# NinjaPool-171009.net
KiCad netlist of a schematic drawn in EAGLE
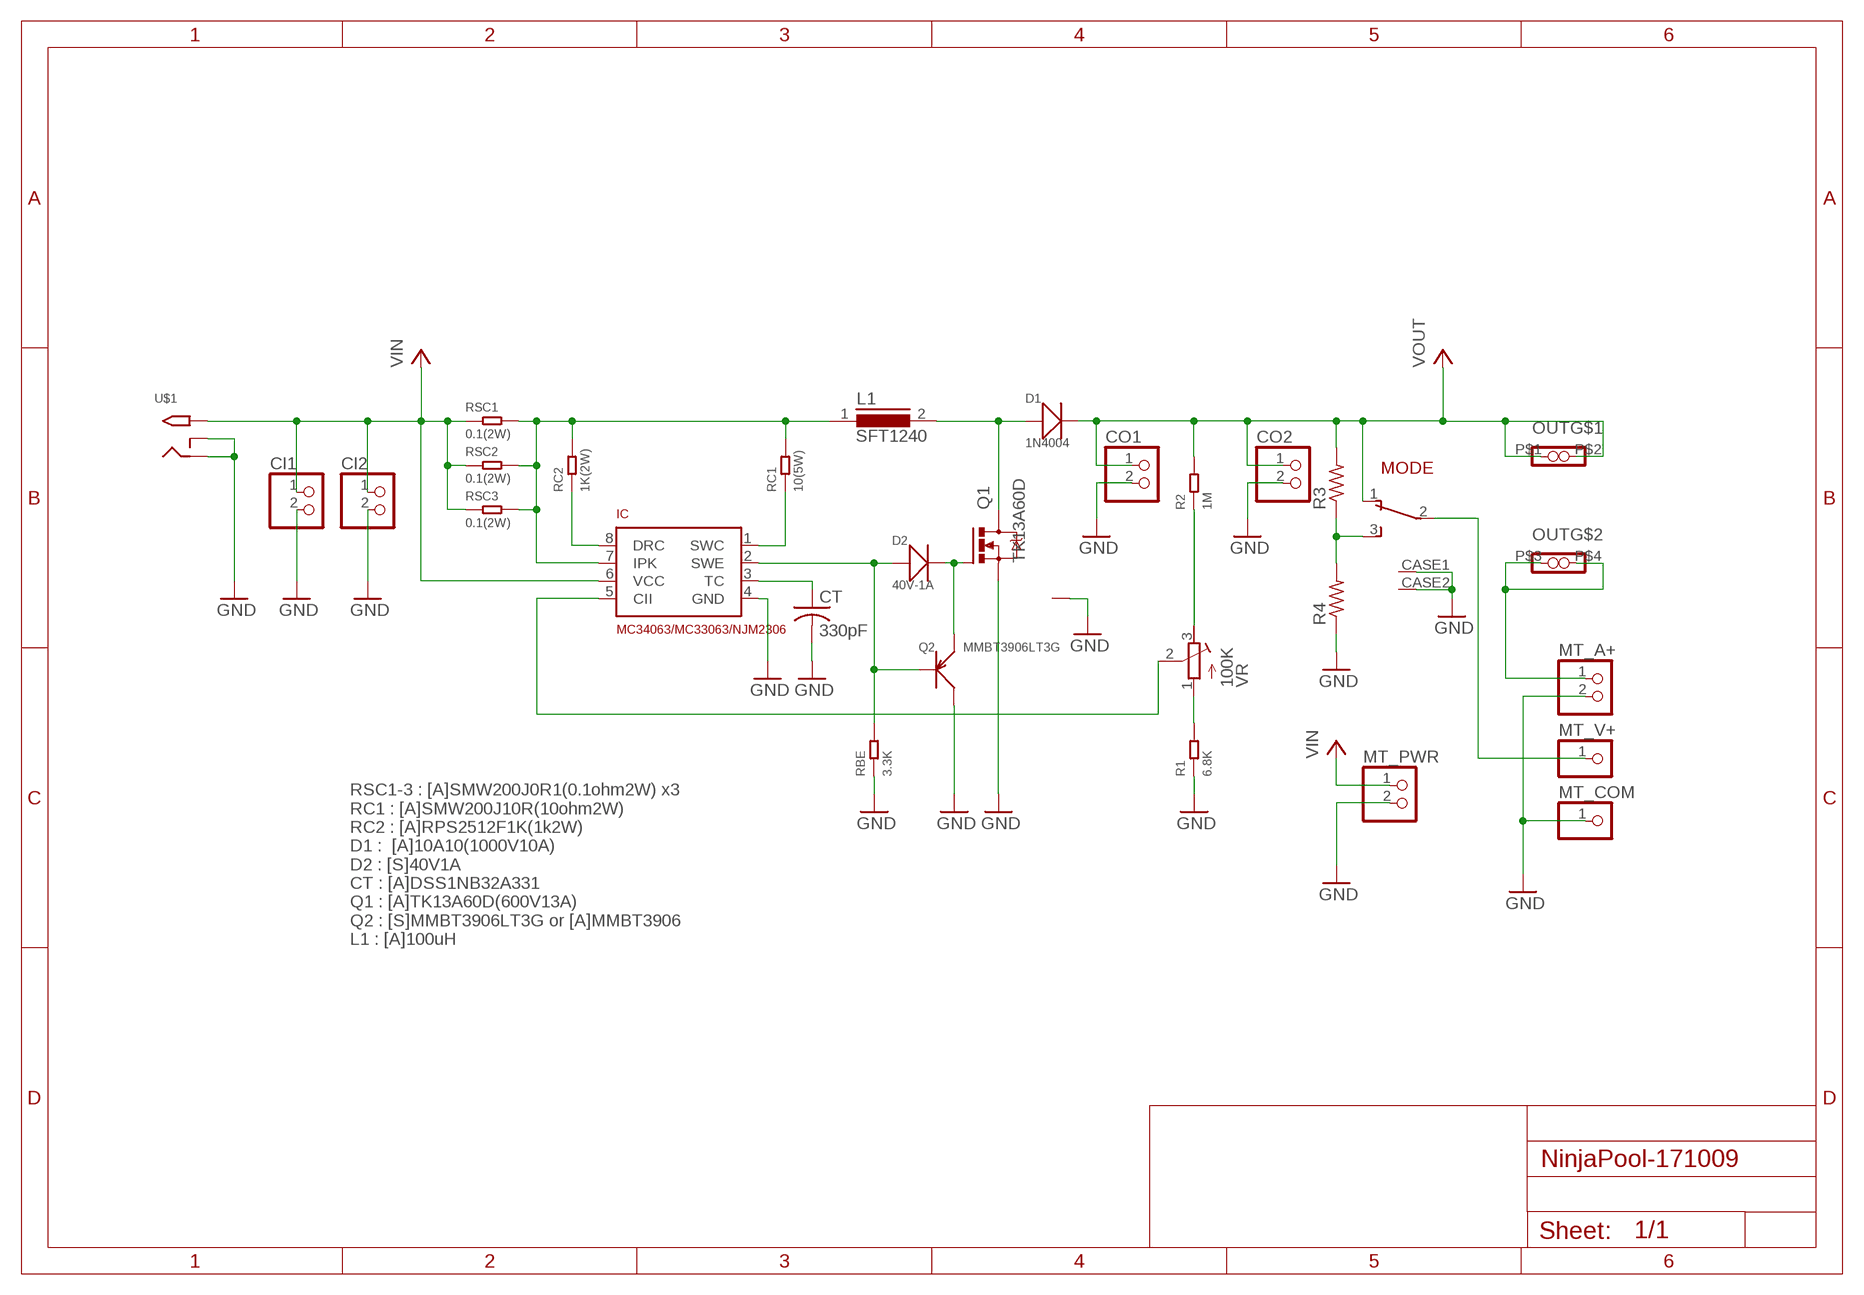
[diagram p0: schematic, sheet 1]

(export (version "E")
  (design (tool "Eeschema 10.0.6"))
  (components
    (comp (ref "CI1")
      (value "PINHD-1X2")
      (footprint "eagle-import:1X02")
      (libsource (lib "eagle-import") (part "PINHD-1X2"))
    )
    (comp (ref "CI2")
      (value "PINHD-1X2")
      (footprint "eagle-import:1X02")
      (libsource (lib "eagle-import") (part "PINHD-1X2"))
    )
    (comp (ref "CO1")
      (value "PINHD-1X2")
      (footprint "eagle-import:1X02")
      (libsource (lib "eagle-import") (part "PINHD-1X2"))
    )
    (comp (ref "CO2")
      (value "PINHD-1X2")
      (footprint "eagle-import:1X02")
      (libsource (lib "eagle-import") (part "PINHD-1X2"))
    )
    (comp (ref "CT")
      (value "330pF")
      (footprint "eagle-import:C050-024X044")
      (libsource (lib "eagle-import") (part "C-US050-024X044"))
    )
    (comp (ref "D1")
      (value "1N4004")
      (footprint "eagle-import:DO-41")
      (libsource (lib "eagle-import") (part "DIP-DIODE-400V-1A(DO-41)"))
    )
    (comp (ref "D2")
      (value "40V-1A")
      (footprint "eagle-import:DO-214AC")
      (fields (field (name "MPN") "1N5819"))
      (libsource (lib "eagle-import") (part "SMD-DIODE-SCHOTTKY-40V-1A(DO-214AC)"))
    )
    (comp (ref "HEAT")
      (value "HEAT111PB015")
      (footprint "eagle-import:HEAT11PB015")
      (libsource (lib "eagle-import") (part "HEAT111PB015"))
    )
    (comp (ref "IC")
      (value "MC34063/MC33063/NJM2306")
      (footprint "eagle-import:DIL8")
      (libsource (lib "eagle-import") (part "MC34063/MC33063/NJM2306"))
    )
    (comp (ref "L1")
      (value "SFT1240")
      (footprint "eagle-import:SFT1240")
      (libsource (lib "eagle-import") (part "SFT1240"))
    )
    (comp (ref "MODE")
      (value "4MS1R202M6QES")
      (footprint "eagle-import:4MS1R202M6QES")
      (libsource (lib "eagle-import") (part "4MS1R202M6QES"))
    )
    (comp (ref "MT_A+")
      (value "PINHD-1X2")
      (footprint "eagle-import:1X02")
      (libsource (lib "eagle-import") (part "PINHD-1X2"))
    )
    (comp (ref "MT_COM")
      (value "PINHD-1X1")
      (footprint "eagle-import:1X01")
      (libsource (lib "eagle-import") (part "PINHD-1X1"))
    )
    (comp (ref "MT_PWR")
      (value "PINHD-1X2")
      (footprint "eagle-import:1X02")
      (libsource (lib "eagle-import") (part "PINHD-1X2"))
    )
    (comp (ref "MT_V+")
      (value "PINHD-1X1")
      (footprint "eagle-import:1X01")
      (libsource (lib "eagle-import") (part "PINHD-1X1"))
    )
    (comp (ref "OUT")
      (value "BANANA")
      (footprint "eagle-import:BANANA_TMP")
      (libsource (lib "eagle-import") (part "BANANA"))
    )
    (comp (ref "Q1")
      (value "TK13A60D")
      (footprint "eagle-import:TO220BV")
      (libsource (lib "eagle-import") (part "IRF520"))
    )
    (comp (ref "Q2")
      (value "MMBT3906LT3G")
      (footprint "eagle-import:SOT-23")
      (libsource (lib "eagle-import") (part "SMD-TRANSISTORS-PNP-40V-200MA-MMBT3906LT3G(SOT-23)"))
    )
    (comp (ref "R1")
      (value "6.8K")
      (footprint "eagle-import:R0603")
      (fields (field (name "MPN") "RC0805JR-07220KL"))
      (libsource (lib "eagle-import") (part "SMD-RES-6.8K-1%-1/10W(0603)"))
    )
    (comp (ref "R2")
      (value "1M")
      (footprint "eagle-import:R0603")
      (fields (field (name "MPN") "RC0603FR-071ML"))
      (libsource (lib "eagle-import") (part "SMD-RES-1M-1%-1/10W(0603)"))
    )
    (comp (ref "R3")
      (value "R-US_R0603")
      (footprint "eagle-import:R0603")
      (libsource (lib "eagle-import") (part "R-US_R0603"))
    )
    (comp (ref "R4")
      (value "R-US_R0603")
      (footprint "eagle-import:R0603")
      (libsource (lib "eagle-import") (part "R-US_R0603"))
    )
    (comp (ref "RBE")
      (value "3.3K")
      (footprint "eagle-import:R0603")
      (libsource (lib "eagle-import") (part "SMD-RES-3.3K-5%-1/10W(0603)"))
    )
    (comp (ref "RC1")
      (value "10(5W)")
      (footprint "eagle-import:SWE500")
      (libsource (lib "eagle-import") (part "SWE500"))
    )
    (comp (ref "RC2")
      (value "1K(2W)")
      (footprint "eagle-import:R2512")
      (libsource (lib "eagle-import") (part "R2512"))
    )
    (comp (ref "RSC1")
      (value "0.1(2W)")
      (footprint "eagle-import:SMW200")
      (libsource (lib "eagle-import") (part "SWE200"))
    )
    (comp (ref "RSC2")
      (value "0.1(2W)")
      (footprint "eagle-import:SMW200")
      (libsource (lib "eagle-import") (part "SWE200"))
    )
    (comp (ref "RSC3")
      (value "0.1(2W)")
      (footprint "eagle-import:SMW200")
      (libsource (lib "eagle-import") (part "SWE200"))
    )
    (comp (ref "U$1")
      (value "2.1MMJACKTHM")
      (footprint "eagle-import:PJ-102A")
      (libsource (lib "eagle-import") (part "2.1MMJACKTHM"))
    )
    (comp (ref "VR")
      (value "100K")
      (footprint "eagle-import:AITENDO_R16K1")
      (libsource (lib "eagle-import") (part "R-TRIMMAITENDO_R16K1"))
    )
  )
  (nets
    (net (code "1") (name "GND") (class "Default")
      (node (ref "CI1") (pin "2") (pinfunction "2_2") (pintype "passive"))
      (node (ref "CI2") (pin "2") (pinfunction "2_2") (pintype "passive"))
      (node (ref "CO1") (pin "2") (pinfunction "2_2") (pintype "passive"))
      (node (ref "CO2") (pin "2") (pinfunction "2_2") (pintype "passive"))
      (node (ref "CT") (pin "2") (pinfunction "2_2") (pintype "passive"))
      (node (ref "HEAT") (pin "P$1") (pinfunction "P$1_P$1") (pintype "bidirectional"))
      (node (ref "IC") (pin "4") (pinfunction "GND_4") (pintype "bidirectional"))
      (node (ref "MODE") (pin "CASE1") (pinfunction "CASE1_CASE1") (pintype "passive"))
      (node (ref "MODE") (pin "CASE2") (pinfunction "CASE2_CASE2") (pintype "passive"))
      (node (ref "MT_A+") (pin "2") (pinfunction "2_2") (pintype "passive"))
      (node (ref "MT_COM") (pin "1") (pinfunction "1_1") (pintype "passive"))
      (node (ref "MT_PWR") (pin "2") (pinfunction "2_2") (pintype "passive"))
      (node (ref "Q1") (pin "S") (pinfunction "S_S") (pintype "passive"))
      (node (ref "Q2") (pin "3") (pinfunction "C_3") (pintype "passive"))
      (node (ref "R1") (pin "1") (pinfunction "1_1") (pintype "passive"))
      (node (ref "R4") (pin "1") (pinfunction "1_1") (pintype "passive"))
      (node (ref "RBE") (pin "1") (pinfunction "1_1") (pintype "passive"))
      (node (ref "U$1") (pin "RING") (pinfunction "RING_RING") (pintype "bidirectional"))
      (node (ref "U$1") (pin "RING_SW") (pinfunction "RING_SW_RING_SW") (pintype "bidirectional"))
    )
    (net (code "2") (name "Net-(D1-+)") (class "Default")
      (node (ref "D1") (pin "1") (pinfunction "+_1") (pintype "passive"))
      (node (ref "L1") (pin "2") (pinfunction "2_2") (pintype "passive"))
      (node (ref "Q1") (pin "D") (pinfunction "D_D") (pintype "passive"))
    )
    (net (code "3") (name "Net-(D2-+)") (class "Default")
      (node (ref "D2") (pin "1") (pinfunction "+_1") (pintype "passive"))
      (node (ref "IC") (pin "2") (pinfunction "SWE_2") (pintype "bidirectional"))
      (node (ref "Q2") (pin "1") (pinfunction "B_1") (pintype "passive"))
      (node (ref "RBE") (pin "2") (pinfunction "2_2") (pintype "passive"))
    )
    (net (code "4") (name "Net-(D2--)") (class "Default")
      (node (ref "D2") (pin "2") (pinfunction "-_2") (pintype "passive"))
      (node (ref "Q1") (pin "G") (pinfunction "G_G") (pintype "passive"))
      (node (ref "Q2") (pin "2") (pinfunction "E_2") (pintype "passive"))
    )
    (net (code "5") (name "Net-(IC-CII)") (class "Default")
      (node (ref "IC") (pin "5") (pinfunction "CII_5") (pintype "bidirectional"))
      (node (ref "VR") (pin "2") (pinfunction "S_2") (pintype "passive"))
    )
    (net (code "6") (name "Net-(IC-DRC)") (class "Default")
      (node (ref "IC") (pin "8") (pinfunction "DRC_8") (pintype "bidirectional"))
      (node (ref "RC2") (pin "1") (pinfunction "1_1") (pintype "passive"))
    )
    (net (code "7") (name "Net-(IC-IPK)") (class "Default")
      (node (ref "IC") (pin "7") (pinfunction "IPK_7") (pintype "bidirectional"))
      (node (ref "L1") (pin "1") (pinfunction "1_1") (pintype "passive"))
      (node (ref "RC1") (pin "2") (pinfunction "2_2") (pintype "passive"))
      (node (ref "RC2") (pin "2") (pinfunction "2_2") (pintype "passive"))
      (node (ref "RSC1") (pin "2") (pinfunction "2_2") (pintype "passive"))
      (node (ref "RSC2") (pin "2") (pinfunction "2_2") (pintype "passive"))
      (node (ref "RSC3") (pin "2") (pinfunction "2_2") (pintype "passive"))
    )
    (net (code "8") (name "Net-(IC-SWC)") (class "Default")
      (node (ref "IC") (pin "1") (pinfunction "SWC_1") (pintype "bidirectional"))
      (node (ref "RC1") (pin "1") (pinfunction "1_1") (pintype "passive"))
    )
    (net (code "9") (name "Net-(IC-TC)") (class "Default")
      (node (ref "CT") (pin "1") (pinfunction "1_1") (pintype "passive"))
      (node (ref "IC") (pin "3") (pinfunction "TC_3") (pintype "bidirectional"))
    )
    (net (code "10") (name "Net-(MODE-Pad2)") (class "Default")
      (node (ref "MODE") (pin "2") (pinfunction "2_2") (pintype "passive"))
      (node (ref "MT_V+") (pin "1") (pinfunction "1_1") (pintype "passive"))
    )
    (net (code "11") (name "Net-(MODE-Pad3)") (class "Default")
      (node (ref "MODE") (pin "3") (pinfunction "3_3") (pintype "passive"))
      (node (ref "R3") (pin "1") (pinfunction "1_1") (pintype "passive"))
      (node (ref "R4") (pin "2") (pinfunction "2_2") (pintype "passive"))
    )
    (net (code "12") (name "Net-(OUTB-1)") (class "Default")
      (node (ref "MT_A+") (pin "1") (pinfunction "1_1") (pintype "passive"))
      (node (ref "OUT") (pin "P$3") (pinfunction "1_P$3") (pintype "passive"))
      (node (ref "OUT") (pin "P$4") (pinfunction "2_P$4") (pintype "passive"))
    )
    (net (code "13") (name "Net-(VR-A)") (class "Default")
      (node (ref "R1") (pin "2") (pinfunction "2_2") (pintype "passive"))
      (node (ref "VR") (pin "1") (pinfunction "A_1") (pintype "passive"))
    )
    (net (code "14") (name "Net-(VR-E)") (class "Default")
      (node (ref "R2") (pin "1") (pinfunction "1_1") (pintype "passive"))
      (node (ref "VR") (pin "3") (pinfunction "E_3") (pintype "passive"))
    )
    (net (code "15") (name "VIN") (class "Default")
      (node (ref "CI1") (pin "1") (pinfunction "1_1") (pintype "passive"))
      (node (ref "CI2") (pin "1") (pinfunction "1_1") (pintype "passive"))
      (node (ref "IC") (pin "6") (pinfunction "VCC_6") (pintype "bidirectional"))
      (node (ref "MT_PWR") (pin "1") (pinfunction "1_1") (pintype "passive"))
      (node (ref "RSC1") (pin "1") (pinfunction "1_1") (pintype "passive"))
      (node (ref "RSC2") (pin "1") (pinfunction "1_1") (pintype "passive"))
      (node (ref "RSC3") (pin "1") (pinfunction "1_1") (pintype "passive"))
      (node (ref "U$1") (pin "TIP") (pinfunction "TIP_TIP") (pintype "bidirectional"))
    )
    (net (code "16") (name "VOUT") (class "Default")
      (node (ref "CO1") (pin "1") (pinfunction "1_1") (pintype "passive"))
      (node (ref "CO2") (pin "1") (pinfunction "1_1") (pintype "passive"))
      (node (ref "D1") (pin "2") (pinfunction "-_2") (pintype "passive"))
      (node (ref "MODE") (pin "1") (pinfunction "1_1") (pintype "passive"))
      (node (ref "OUT") (pin "P$1") (pinfunction "1_P$1") (pintype "passive"))
      (node (ref "OUT") (pin "P$2") (pinfunction "2_P$2") (pintype "passive"))
      (node (ref "R2") (pin "2") (pinfunction "2_2") (pintype "passive"))
      (node (ref "R3") (pin "2") (pinfunction "2_2") (pintype "passive"))
    )
  )
)
